# Actor_6_Channel.net
KiCad netlist of a schematic drawn in EAGLE
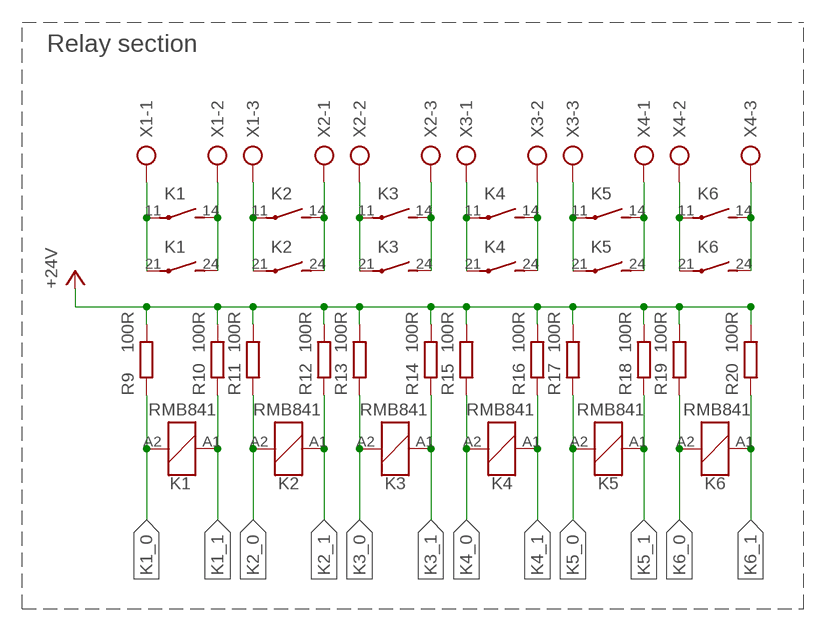
[diagram p0: schematic, sheet 1, part 1 of 2]
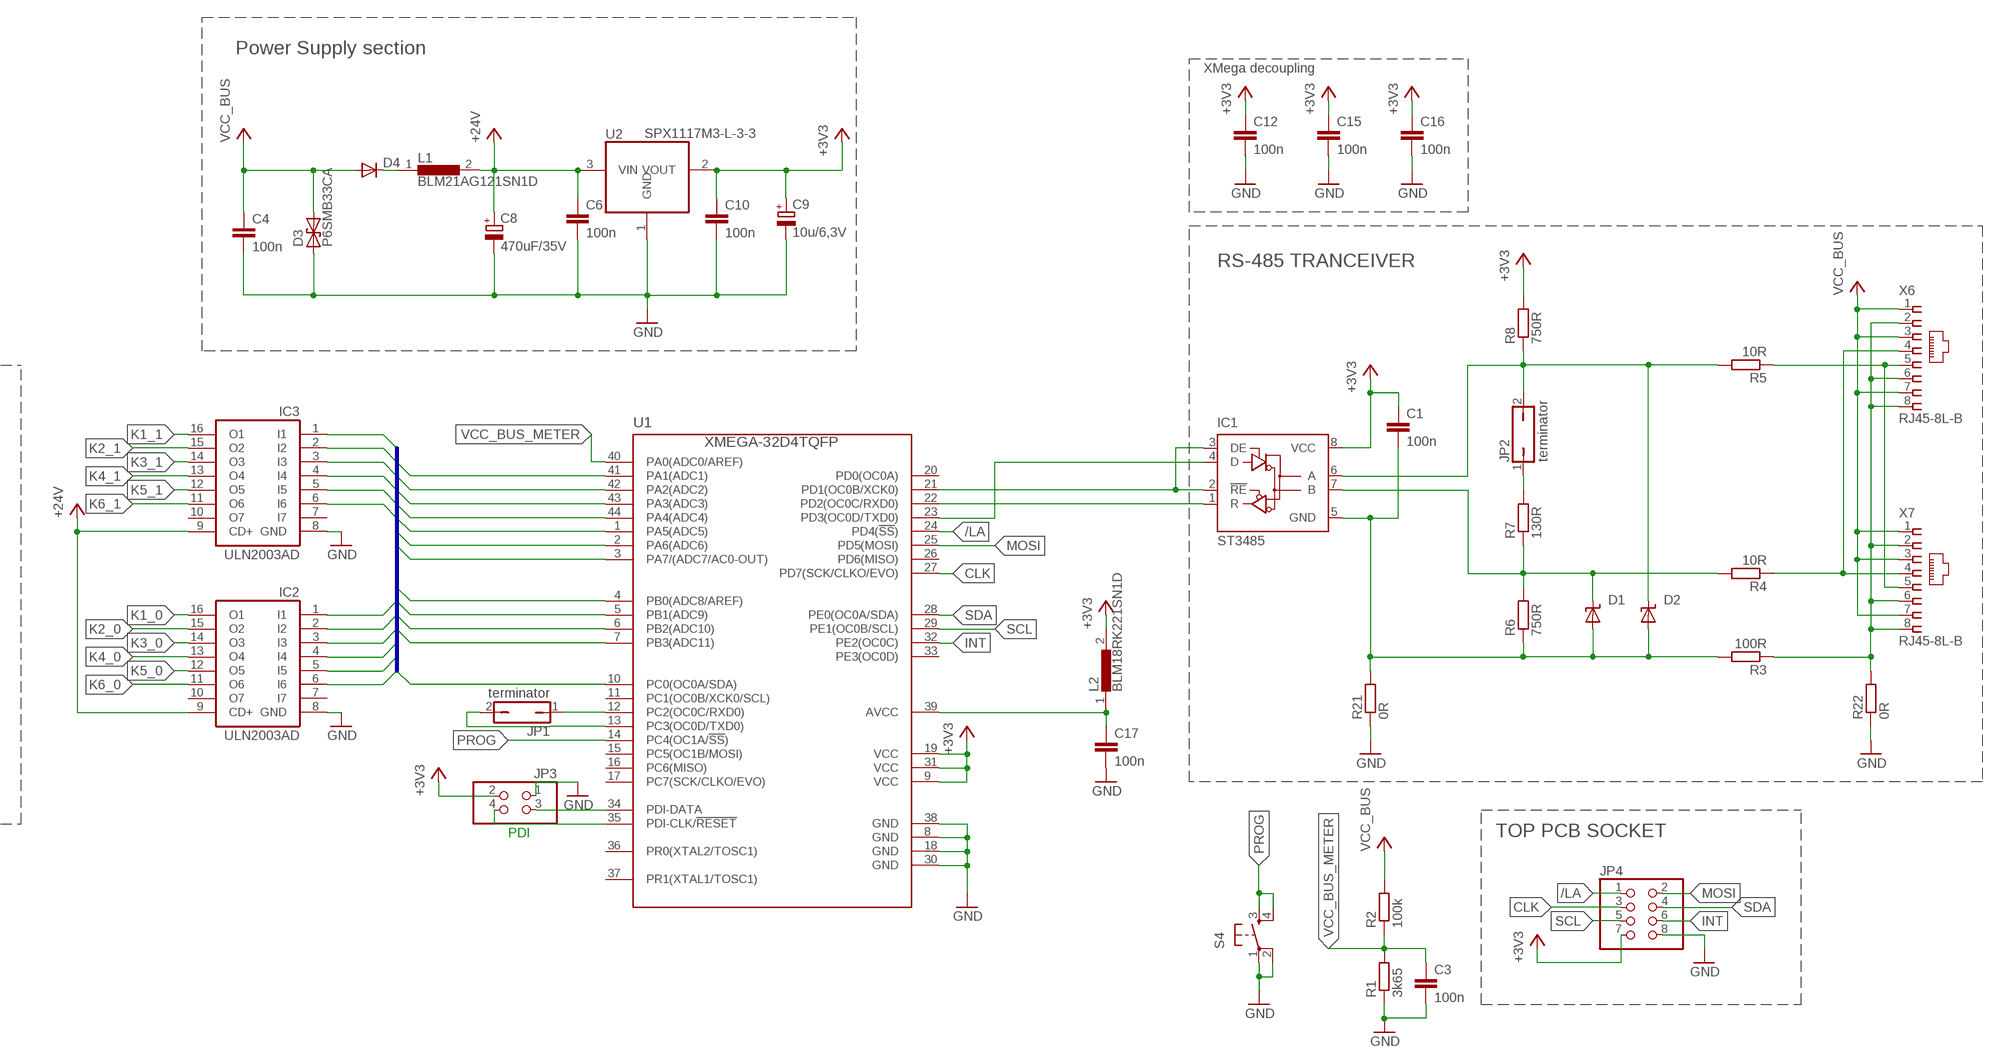
[diagram p1: schematic, sheet 1, part 2 of 2]

(export (version "E")
  (design (tool "Eeschema 10.0.6"))
  (components
    (comp (ref "C1")
      (value "100n")
      (footprint "eagle-import:C0603K")
      (libsource (lib "eagle-import") (part "C-EUC0603K"))
    )
    (comp (ref "C3")
      (value "100n")
      (footprint "eagle-import:C0603K")
      (libsource (lib "eagle-import") (part "C-EUC0603K"))
    )
    (comp (ref "C4")
      (value "100n")
      (footprint "eagle-import:C0603K")
      (libsource (lib "eagle-import") (part "C-EUC0603K"))
    )
    (comp (ref "C6")
      (value "100n")
      (footprint "eagle-import:C0603K")
      (libsource (lib "eagle-import") (part "C-EUC0603K"))
    )
    (comp (ref "C8")
      (value "470uF/35V")
      (footprint "eagle-import:E5-10,5")
      (libsource (lib "eagle-import") (part "CPOL-EUE5-10.5"))
    )
    (comp (ref "C9")
      (value "10u/6,3V")
      (footprint "eagle-import:E2-4")
      (libsource (lib "eagle-import") (part "CPOL-EUE2-4"))
    )
    (comp (ref "C10")
      (value "100n")
      (footprint "eagle-import:C0603K")
      (libsource (lib "eagle-import") (part "C-EUC0603K"))
    )
    (comp (ref "C12")
      (value "100n")
      (footprint "eagle-import:C0603K")
      (libsource (lib "eagle-import") (part "C-EUC0603K"))
    )
    (comp (ref "C15")
      (value "100n")
      (footprint "eagle-import:C0603K")
      (libsource (lib "eagle-import") (part "C-EUC0603K"))
    )
    (comp (ref "C16")
      (value "100n")
      (footprint "eagle-import:C0603K")
      (libsource (lib "eagle-import") (part "C-EUC0603K"))
    )
    (comp (ref "C17")
      (value "100n")
      (footprint "eagle-import:C0603K")
      (libsource (lib "eagle-import") (part "C-EUC0603K"))
    )
    (comp (ref "D1")
      (value "SUPPRESSOR-SMBJ")
      (footprint "eagle-import:SMBJ")
      (libsource (lib "eagle-import") (part "SUPPRESSOR-SMBJ"))
    )
    (comp (ref "D2")
      (value "SUPPRESSOR-SMBJ")
      (footprint "eagle-import:SMBJ")
      (libsource (lib "eagle-import") (part "SUPPRESSOR-SMBJ"))
    )
    (comp (ref "D3")
      (value "P6SMB33CA")
      (footprint "eagle-import:DO214AA")
      (libsource (lib "eagle-import") (part "P6KEXXCSMD"))
    )
    (comp (ref "D4")
      (value "DIODE-DO214AA")
      (footprint "eagle-import:DO214AA")
      (libsource (lib "eagle-import") (part "DIODE-DO214AA"))
    )
    (comp (ref "IC1")
      (value "ST3485")
      (footprint "eagle-import:D_R-PDSO-G8")
      (libsource (lib "eagle-import") (part "75176AD"))
    )
    (comp (ref "IC2")
      (value "ULN2003AD")
      (footprint "eagle-import:SO16")
      (libsource (lib "eagle-import") (part "ULN2003AD"))
    )
    (comp (ref "IC3")
      (value "ULN2003AD")
      (footprint "eagle-import:SO16")
      (libsource (lib "eagle-import") (part "ULN2003AD"))
    )
    (comp (ref "JP1")
      (value "terminator")
      (footprint "eagle-import:JP1")
      (libsource (lib "eagle-import") (part "JP1Q"))
    )
    (comp (ref "JP2")
      (value "terminator")
      (footprint "eagle-import:JP1")
      (libsource (lib "eagle-import") (part "JP1Q"))
    )
    (comp (ref "JP3")
      (value "PINHD-2X2")
      (footprint "eagle-import:2X02")
      (libsource (lib "eagle-import") (part "PINHD-2X2"))
    )
    (comp (ref "JP4")
      (value "PINHD-2X4")
      (footprint "eagle-import:2X04")
      (libsource (lib "eagle-import") (part "PINHD-2X4"))
    )
    (comp (ref "K1")
      (value "RMB841")
      (footprint "eagle-import:RT2N_O")
      (libsource (lib "eagle-import") (part "RT44?4730"))
    )
    (comp (ref "K2")
      (value "RMB841")
      (footprint "eagle-import:RT2N_O")
      (fields (field (name "OC_FARNELL") "unknown") (field (name "OC_NEWARK") "unknown"))
      (libsource (lib "eagle-import") (part "RT44?4730"))
    )
    (comp (ref "K3")
      (value "RMB841")
      (footprint "eagle-import:RT2N_O")
      (fields (field (name "OC_FARNELL") "unknown") (field (name "OC_NEWARK") "unknown"))
      (libsource (lib "eagle-import") (part "RT44?4730"))
    )
    (comp (ref "K4")
      (value "RMB841")
      (footprint "eagle-import:RT2N_O")
      (fields (field (name "OC_FARNELL") "unknown") (field (name "OC_NEWARK") "unknown"))
      (libsource (lib "eagle-import") (part "RT44?4730"))
    )
    (comp (ref "K5")
      (value "RMB841")
      (footprint "eagle-import:RT2N_O")
      (fields (field (name "OC_FARNELL") "unknown") (field (name "OC_NEWARK") "unknown"))
      (libsource (lib "eagle-import") (part "RT44?4730"))
    )
    (comp (ref "K6")
      (value "RMB841")
      (footprint "eagle-import:RT2N_O")
      (fields (field (name "OC_FARNELL") "unknown") (field (name "OC_NEWARK") "unknown"))
      (libsource (lib "eagle-import") (part "RT44?4730"))
    )
    (comp (ref "L1")
      (value "BLM21AG121SN1D")
      (footprint "eagle-import:805")
      (libsource (lib "eagle-import") (part "BLM21AG121SN1D"))
    )
    (comp (ref "L2")
      (value "BLM18RK221SN1D")
      (footprint "eagle-import:0603")
      (libsource (lib "eagle-import") (part "BLM18RK221SN1D"))
    )
    (comp (ref "R1")
      (value "3k65")
      (footprint "eagle-import:R0603")
      (libsource (lib "eagle-import") (part "R-EU_R0603"))
    )
    (comp (ref "R2")
      (value "100k")
      (footprint "eagle-import:R0603")
      (libsource (lib "eagle-import") (part "R-EU_R0603"))
    )
    (comp (ref "R3")
      (value "100R")
      (footprint "eagle-import:R0603")
      (libsource (lib "eagle-import") (part "R-EU_R0603"))
    )
    (comp (ref "R4")
      (value "10R")
      (footprint "eagle-import:R0603")
      (libsource (lib "eagle-import") (part "R-EU_R0603"))
    )
    (comp (ref "R5")
      (value "10R")
      (footprint "eagle-import:R0603")
      (libsource (lib "eagle-import") (part "R-EU_R0603"))
    )
    (comp (ref "R6")
      (value "750R")
      (footprint "eagle-import:M1206")
      (libsource (lib "eagle-import") (part "R-EU_M1206"))
    )
    (comp (ref "R7")
      (value "130R")
      (footprint "eagle-import:R0603")
      (libsource (lib "eagle-import") (part "R-EU_R0603"))
    )
    (comp (ref "R8")
      (value "750R")
      (footprint "eagle-import:R0603")
      (libsource (lib "eagle-import") (part "R-EU_R0603"))
    )
    (comp (ref "R9")
      (value "100R")
      (footprint "eagle-import:R0603")
      (libsource (lib "eagle-import") (part "R-EU_R0603"))
    )
    (comp (ref "R10")
      (value "100R")
      (footprint "eagle-import:R0603")
      (libsource (lib "eagle-import") (part "R-EU_R0603"))
    )
    (comp (ref "R11")
      (value "100R")
      (footprint "eagle-import:R0603")
      (libsource (lib "eagle-import") (part "R-EU_R0603"))
    )
    (comp (ref "R12")
      (value "100R")
      (footprint "eagle-import:R0603")
      (libsource (lib "eagle-import") (part "R-EU_R0603"))
    )
    (comp (ref "R13")
      (value "100R")
      (footprint "eagle-import:R0603")
      (libsource (lib "eagle-import") (part "R-EU_R0603"))
    )
    (comp (ref "R14")
      (value "100R")
      (footprint "eagle-import:R0603")
      (libsource (lib "eagle-import") (part "R-EU_R0603"))
    )
    (comp (ref "R15")
      (value "100R")
      (footprint "eagle-import:R0603")
      (libsource (lib "eagle-import") (part "R-EU_R0603"))
    )
    (comp (ref "R16")
      (value "100R")
      (footprint "eagle-import:R0603")
      (libsource (lib "eagle-import") (part "R-EU_R0603"))
    )
    (comp (ref "R17")
      (value "100R")
      (footprint "eagle-import:R0603")
      (libsource (lib "eagle-import") (part "R-EU_R0603"))
    )
    (comp (ref "R18")
      (value "100R")
      (footprint "eagle-import:R0603")
      (libsource (lib "eagle-import") (part "R-EU_R0603"))
    )
    (comp (ref "R19")
      (value "100R")
      (footprint "eagle-import:R0603")
      (libsource (lib "eagle-import") (part "R-EU_R0603"))
    )
    (comp (ref "R20")
      (value "100R")
      (footprint "eagle-import:R0603")
      (libsource (lib "eagle-import") (part "R-EU_R0603"))
    )
    (comp (ref "R21")
      (value "0R")
      (footprint "eagle-import:R0603")
      (libsource (lib "eagle-import") (part "R-EU_R0603"))
    )
    (comp (ref "R22")
      (value "0R")
      (footprint "eagle-import:R0603")
      (libsource (lib "eagle-import") (part "R-EU_R0603"))
    )
    (comp (ref "S4")
      (value "SPARKFUN_TAC_SWITCHPTH")
      (footprint "eagle-import:SPARKFUN_TACTILE-PTH")
      (libsource (lib "eagle-import") (part "SPARKFUN_TAC_SWITCHPTH"))
    )
    (comp (ref "U1")
      (value "XMEGA-32D4TQFP")
      (footprint "eagle-import:TQFP44")
      (libsource (lib "eagle-import") (part "XMEGA-D4TQFP"))
    )
    (comp (ref "U2")
      (value "SPX1117M3-L-3-3")
      (footprint "eagle-import:SOT223")
      (fields (field (name "MPN") "REG1117"))
      (libsource (lib "eagle-import") (part "REG1117"))
    )
    (comp (ref "X1")
      (value "MKDS_5/3-7,5")
      (footprint "eagle-import:MKDS_5_-750")
      (libsource (lib "eagle-import") (part "MKDS_5/3-7,5"))
    )
    (comp (ref "X2")
      (value "MKDS_5/3-7,5")
      (footprint "eagle-import:MKDS_5_-750")
      (libsource (lib "eagle-import") (part "MKDS_5/3-7,5"))
    )
    (comp (ref "X3")
      (value "MKDS_5/3-7,5")
      (footprint "eagle-import:MKDS_5_-750")
      (libsource (lib "eagle-import") (part "MKDS_5/3-7,5"))
    )
    (comp (ref "X4")
      (value "MKDS_5/3-7,5")
      (footprint "eagle-import:MKDS_5_-750")
      (libsource (lib "eagle-import") (part "MKDS_5/3-7,5"))
    )
    (comp (ref "X6")
      (value "RJ45-8L-B")
      (footprint "eagle-import:RJ45-NO-SHIELD")
      (fields (field (name "MF") "TYCO ELECTRONICS"))
      (libsource (lib "eagle-import") (part "RJ45-8L-B"))
    )
    (comp (ref "X7")
      (value "RJ45-8L-B")
      (footprint "eagle-import:RJ45-NO-SHIELD")
      (fields (field (name "MF") "TYCO ELECTRONICS"))
      (libsource (lib "eagle-import") (part "RJ45-8L-B"))
    )
  )
  (nets
    (net (code "1") (name "+3V3") (class "Default")
      (node (ref "C1") (pin "1") (pinfunction "1_1") (pintype "passive"))
      (node (ref "C10") (pin "1") (pinfunction "1_1") (pintype "passive"))
      (node (ref "C12") (pin "1") (pinfunction "1_1") (pintype "passive"))
      (node (ref "C15") (pin "1") (pinfunction "1_1") (pintype "passive"))
      (node (ref "C16") (pin "1") (pinfunction "1_1") (pintype "passive"))
      (node (ref "C9") (pin "+") (pinfunction "+_+") (pintype "passive"))
      (node (ref "IC1") (pin "8") (pinfunction "VCC_8") (pintype "power_in"))
      (node (ref "JP3") (pin "2") (pinfunction "2_2") (pintype "passive"))
      (node (ref "JP4") (pin "7") (pinfunction "7_7") (pintype "passive"))
      (node (ref "L2") (pin "2") (pinfunction "2_2") (pintype "passive"))
      (node (ref "R8") (pin "2") (pinfunction "2_2") (pintype "passive"))
      (node (ref "U1") (pin "19") (pinfunction "VCC_19") (pintype "power_in"))
      (node (ref "U1") (pin "31") (pinfunction "VCC_31") (pintype "power_in"))
      (node (ref "U1") (pin "9") (pinfunction "VCC_9") (pintype "power_in"))
      (node (ref "U2") (pin "2") (pinfunction "VOUT_2") (pintype "output"))
    )
    (net (code "2") (name "+24V") (class "Default")
      (node (ref "C6") (pin "1") (pinfunction "1_1") (pintype "passive"))
      (node (ref "C8") (pin "+") (pinfunction "+_+") (pintype "passive"))
      (node (ref "IC2") (pin "9") (pinfunction "CD+_9") (pintype "passive"))
      (node (ref "IC3") (pin "9") (pinfunction "CD+_9") (pintype "passive"))
      (node (ref "L1") (pin "2") (pinfunction "2_2") (pintype "passive"))
      (node (ref "R10") (pin "2") (pinfunction "2_2") (pintype "passive"))
      (node (ref "R11") (pin "2") (pinfunction "2_2") (pintype "passive"))
      (node (ref "R12") (pin "2") (pinfunction "2_2") (pintype "passive"))
      (node (ref "R13") (pin "2") (pinfunction "2_2") (pintype "passive"))
      (node (ref "R14") (pin "2") (pinfunction "2_2") (pintype "passive"))
      (node (ref "R15") (pin "2") (pinfunction "2_2") (pintype "passive"))
      (node (ref "R16") (pin "2") (pinfunction "2_2") (pintype "passive"))
      (node (ref "R17") (pin "2") (pinfunction "2_2") (pintype "passive"))
      (node (ref "R18") (pin "2") (pinfunction "2_2") (pintype "passive"))
      (node (ref "R19") (pin "2") (pinfunction "2_2") (pintype "passive"))
      (node (ref "R20") (pin "2") (pinfunction "2_2") (pintype "passive"))
      (node (ref "R9") (pin "2") (pinfunction "2_2") (pintype "passive"))
      (node (ref "U2") (pin "3") (pinfunction "VIN_3") (pintype "input"))
    )
    (net (code "3") (name "/PA1") (class "Default")
      (node (ref "IC3") (pin "6") (pinfunction "I6_6") (pintype "input"))
      (node (ref "U1") (pin "41") (pinfunction "PA1(ADC1)_41") (pintype "bidirectional"))
    )
    (net (code "4") (name "/PA2") (class "Default")
      (node (ref "IC3") (pin "5") (pinfunction "I5_5") (pintype "input"))
      (node (ref "U1") (pin "42") (pinfunction "PA2(ADC2)_42") (pintype "bidirectional"))
    )
    (net (code "5") (name "/PA3") (class "Default")
      (node (ref "IC3") (pin "4") (pinfunction "I4_4") (pintype "input"))
      (node (ref "U1") (pin "43") (pinfunction "PA3(ADC3)_43") (pintype "bidirectional"))
    )
    (net (code "6") (name "/PA4") (class "Default")
      (node (ref "IC3") (pin "3") (pinfunction "I3_3") (pintype "input"))
      (node (ref "U1") (pin "44") (pinfunction "PA4(ADC4)_44") (pintype "bidirectional"))
    )
    (net (code "7") (name "/PA5") (class "Default")
      (node (ref "IC3") (pin "2") (pinfunction "I2_2") (pintype "input"))
      (node (ref "U1") (pin "1") (pinfunction "PA5(ADC5)_1") (pintype "bidirectional"))
    )
    (net (code "8") (name "/PA6") (class "Default")
      (node (ref "IC3") (pin "1") (pinfunction "I1_1") (pintype "input"))
      (node (ref "U1") (pin "2") (pinfunction "PA6(ADC6)_2") (pintype "bidirectional"))
    )
    (net (code "9") (name "/PA7") (class "Default")
      (node (ref "IC2") (pin "6") (pinfunction "I6_6") (pintype "input"))
      (node (ref "U1") (pin "3") (pinfunction "PA7/(ADC7/AC0-OUT)_3") (pintype "bidirectional"))
    )
    (net (code "10") (name "/PB0") (class "Default")
      (node (ref "IC2") (pin "5") (pinfunction "I5_5") (pintype "input"))
      (node (ref "U1") (pin "4") (pinfunction "PB0(ADC8/AREF)_4") (pintype "bidirectional"))
    )
    (net (code "11") (name "/PB1") (class "Default")
      (node (ref "IC2") (pin "4") (pinfunction "I4_4") (pintype "input"))
      (node (ref "U1") (pin "5") (pinfunction "PB1(ADC9)_5") (pintype "bidirectional"))
    )
    (net (code "12") (name "/PB2") (class "Default")
      (node (ref "IC2") (pin "3") (pinfunction "I3_3") (pintype "input"))
      (node (ref "U1") (pin "6") (pinfunction "PB2(ADC10)_6") (pintype "bidirectional"))
    )
    (net (code "13") (name "/PB3") (class "Default")
      (node (ref "IC2") (pin "2") (pinfunction "I2_2") (pintype "input"))
      (node (ref "U1") (pin "7") (pinfunction "PB3(ADC11)_7") (pintype "bidirectional"))
    )
    (net (code "14") (name "/PC0") (class "Default")
      (node (ref "IC2") (pin "1") (pinfunction "I1_1") (pintype "input"))
      (node (ref "U1") (pin "10") (pinfunction "PC0(OC0A/SDA)_10") (pintype "bidirectional"))
    )
    (net (code "15") (name "CLK") (class "Default")
      (node (ref "JP4") (pin "3") (pinfunction "3_3") (pintype "passive"))
      (node (ref "U1") (pin "27") (pinfunction "PD7(SCK/CLKO/EVO)_27") (pintype "bidirectional"))
    )
    (net (code "16") (name "GND") (class "Default")
      (node (ref "C10") (pin "2") (pinfunction "2_2") (pintype "passive"))
      (node (ref "C12") (pin "2") (pinfunction "2_2") (pintype "passive"))
      (node (ref "C15") (pin "2") (pinfunction "2_2") (pintype "passive"))
      (node (ref "C16") (pin "2") (pinfunction "2_2") (pintype "passive"))
      (node (ref "C17") (pin "2") (pinfunction "2_2") (pintype "passive"))
      (node (ref "C3") (pin "2") (pinfunction "2_2") (pintype "passive"))
      (node (ref "C4") (pin "2") (pinfunction "2_2") (pintype "passive"))
      (node (ref "C6") (pin "2") (pinfunction "2_2") (pintype "passive"))
      (node (ref "C8") (pin "-") (pinfunction "-_-") (pintype "passive"))
      (node (ref "C9") (pin "-") (pinfunction "-_-") (pintype "passive"))
      (node (ref "D3") (pin "A") (pinfunction "1_A") (pintype "passive"))
      (node (ref "IC2") (pin "8") (pinfunction "GND_8") (pintype "power_in"))
      (node (ref "IC3") (pin "8") (pinfunction "GND_8") (pintype "power_in"))
      (node (ref "JP3") (pin "1") (pinfunction "1_1") (pintype "passive"))
      (node (ref "JP4") (pin "8") (pinfunction "8_8") (pintype "passive"))
      (node (ref "R1") (pin "1") (pinfunction "1_1") (pintype "passive"))
      (node (ref "R21") (pin "1") (pinfunction "1_1") (pintype "passive"))
      (node (ref "R22") (pin "1") (pinfunction "1_1") (pintype "passive"))
      (node (ref "S4") (pin "1") (pinfunction "1_1") (pintype "passive"))
      (node (ref "S4") (pin "2") (pinfunction "2_2") (pintype "passive"))
      (node (ref "U1") (pin "18") (pinfunction "GND_18") (pintype "power_in"))
      (node (ref "U1") (pin "30") (pinfunction "GND_30") (pintype "power_in"))
      (node (ref "U1") (pin "38") (pinfunction "GND_38") (pintype "power_in"))
      (node (ref "U1") (pin "8") (pinfunction "GND_8") (pintype "power_in"))
      (node (ref "U2") (pin "1") (pinfunction "GND_1") (pintype "power_in"))
    )
    (net (code "17") (name "INT") (class "Default")
      (node (ref "JP4") (pin "6") (pinfunction "6_6") (pintype "passive"))
      (node (ref "U1") (pin "32") (pinfunction "PE2(OC0C)_32") (pintype "bidirectional"))
    )
    (net (code "18") (name "K1_0") (class "Default")
      (node (ref "IC2") (pin "16") (pinfunction "O1_16") (pintype "open_collector"))
      (node (ref "K1") (pin "A2") (pinfunction "1_A2") (pintype "passive"))
      (node (ref "R9") (pin "1") (pinfunction "1_1") (pintype "passive"))
    )
    (net (code "19") (name "K1_1") (class "Default")
      (node (ref "IC3") (pin "16") (pinfunction "O1_16") (pintype "open_collector"))
      (node (ref "K1") (pin "A1") (pinfunction "2_A1") (pintype "passive"))
      (node (ref "R10") (pin "1") (pinfunction "1_1") (pintype "passive"))
    )
    (net (code "20") (name "K2_0") (class "Default")
      (node (ref "IC2") (pin "15") (pinfunction "O2_15") (pintype "open_collector"))
      (node (ref "K2") (pin "A2") (pinfunction "1_A2") (pintype "passive"))
      (node (ref "R11") (pin "1") (pinfunction "1_1") (pintype "passive"))
    )
    (net (code "21") (name "K2_1") (class "Default")
      (node (ref "IC3") (pin "15") (pinfunction "O2_15") (pintype "open_collector"))
      (node (ref "K2") (pin "A1") (pinfunction "2_A1") (pintype "passive"))
      (node (ref "R12") (pin "1") (pinfunction "1_1") (pintype "passive"))
    )
    (net (code "22") (name "K3_0") (class "Default")
      (node (ref "IC2") (pin "14") (pinfunction "O3_14") (pintype "open_collector"))
      (node (ref "K3") (pin "A2") (pinfunction "1_A2") (pintype "passive"))
      (node (ref "R13") (pin "1") (pinfunction "1_1") (pintype "passive"))
    )
    (net (code "23") (name "K3_1") (class "Default")
      (node (ref "IC3") (pin "14") (pinfunction "O3_14") (pintype "open_collector"))
      (node (ref "K3") (pin "A1") (pinfunction "2_A1") (pintype "passive"))
      (node (ref "R14") (pin "1") (pinfunction "1_1") (pintype "passive"))
    )
    (net (code "24") (name "K4_0") (class "Default")
      (node (ref "IC2") (pin "13") (pinfunction "O4_13") (pintype "open_collector"))
      (node (ref "K4") (pin "A2") (pinfunction "1_A2") (pintype "passive"))
      (node (ref "R15") (pin "1") (pinfunction "1_1") (pintype "passive"))
    )
    (net (code "25") (name "K4_1") (class "Default")
      (node (ref "IC3") (pin "13") (pinfunction "O4_13") (pintype "open_collector"))
      (node (ref "K4") (pin "A1") (pinfunction "2_A1") (pintype "passive"))
      (node (ref "R16") (pin "1") (pinfunction "1_1") (pintype "passive"))
    )
    (net (code "26") (name "K5_0") (class "Default")
      (node (ref "IC2") (pin "12") (pinfunction "O5_12") (pintype "open_collector"))
      (node (ref "K5") (pin "A2") (pinfunction "1_A2") (pintype "passive"))
      (node (ref "R17") (pin "1") (pinfunction "1_1") (pintype "passive"))
    )
    (net (code "27") (name "K5_1") (class "Default")
      (node (ref "IC3") (pin "12") (pinfunction "O5_12") (pintype "open_collector"))
      (node (ref "K5") (pin "A1") (pinfunction "2_A1") (pintype "passive"))
      (node (ref "R18") (pin "1") (pinfunction "1_1") (pintype "passive"))
    )
    (net (code "28") (name "K6_0") (class "Default")
      (node (ref "IC2") (pin "11") (pinfunction "O6_11") (pintype "open_collector"))
      (node (ref "K6") (pin "A2") (pinfunction "1_A2") (pintype "passive"))
      (node (ref "R19") (pin "1") (pinfunction "1_1") (pintype "passive"))
    )
    (net (code "29") (name "K6_1") (class "Default")
      (node (ref "IC3") (pin "11") (pinfunction "O6_11") (pintype "open_collector"))
      (node (ref "K6") (pin "A1") (pinfunction "2_A1") (pintype "passive"))
      (node (ref "R20") (pin "1") (pinfunction "1_1") (pintype "passive"))
    )
    (net (code "30") (name "MOSI") (class "Default")
      (node (ref "JP4") (pin "2") (pinfunction "2_2") (pintype "passive"))
      (node (ref "U1") (pin "25") (pinfunction "PD5(MOSI)_25") (pintype "bidirectional"))
    )
    (net (code "31") (name "Net-(D4-PadC)") (class "Default")
      (node (ref "D4") (pin "C") (pinfunction "C_C") (pintype "passive"))
      (node (ref "L1") (pin "1") (pinfunction "1_1") (pintype "passive"))
    )
    (net (code "32") (name "Net-(IC1-A)") (class "Default")
      (node (ref "D2") (pin "C") (pinfunction "C_C") (pintype "passive"))
      (node (ref "IC1") (pin "6") (pinfunction "A_6") (pintype "output"))
      (node (ref "JP2") (pin "2") (pinfunction "2_2") (pintype "passive"))
      (node (ref "R5") (pin "2") (pinfunction "2_2") (pintype "passive"))
      (node (ref "R8") (pin "1") (pinfunction "1_1") (pintype "passive"))
    )
    (net (code "33") (name "Net-(IC1-B)") (class "Default")
      (node (ref "D1") (pin "C") (pinfunction "C_C") (pintype "passive"))
      (node (ref "IC1") (pin "7") (pinfunction "B_7") (pintype "output"))
      (node (ref "R4") (pin "2") (pinfunction "2_2") (pintype "passive"))
      (node (ref "R6") (pin "2") (pinfunction "2_2") (pintype "passive"))
      (node (ref "R7") (pin "1") (pinfunction "1_1") (pintype "passive"))
    )
    (net (code "34") (name "Net-(IC1-D)") (class "Default")
      (node (ref "IC1") (pin "4") (pinfunction "D_4") (pintype "input"))
      (node (ref "U1") (pin "23") (pinfunction "PD3(OC0D/TXD0)_23") (pintype "bidirectional"))
    )
    (net (code "35") (name "Net-(IC1-DE)") (class "Default")
      (node (ref "IC1") (pin "2") (pinfunction "~{RE}_2") (pintype "input"))
      (node (ref "IC1") (pin "3") (pinfunction "DE_3") (pintype "input"))
      (node (ref "U1") (pin "21") (pinfunction "PD1(OC0B/XCK0)_21") (pintype "bidirectional"))
    )
    (net (code "36") (name "Net-(IC1-GND)") (class "Default")
      (node (ref "C1") (pin "2") (pinfunction "2_2") (pintype "passive"))
      (node (ref "D1") (pin "A") (pinfunction "A_A") (pintype "passive"))
      (node (ref "D2") (pin "A") (pinfunction "A_A") (pintype "passive"))
      (node (ref "IC1") (pin "5") (pinfunction "GND_5") (pintype "power_in"))
      (node (ref "R21") (pin "2") (pinfunction "2_2") (pintype "passive"))
      (node (ref "R3") (pin "2") (pinfunction "2_2") (pintype "passive"))
      (node (ref "R6") (pin "1") (pinfunction "1_1") (pintype "passive"))
    )
    (net (code "37") (name "Net-(IC1-R)") (class "Default")
      (node (ref "IC1") (pin "1") (pinfunction "R_1") (pintype "input"))
      (node (ref "U1") (pin "22") (pinfunction "PD2(OC0C/RXD0)_22") (pintype "bidirectional"))
    )
    (net (code "38") (name "Net-(JP2-Pad1)") (class "Default")
      (node (ref "JP2") (pin "1") (pinfunction "1_1") (pintype "passive"))
      (node (ref "R7") (pin "2") (pinfunction "2_2") (pintype "passive"))
    )
    (net (code "39") (name "Net-(K1B-P)") (class "Default")
      (node (ref "K1") (pin "11") (pinfunction "P_11") (pintype "passive"))
      (node (ref "K1") (pin "21") (pinfunction "P_21") (pintype "passive"))
      (node (ref "X1") (pin "1") (pinfunction "KL_1") (pintype "passive"))
    )
    (net (code "40") (name "Net-(K1B-S)") (class "Default")
      (node (ref "K1") (pin "14") (pinfunction "S_14") (pintype "passive"))
      (node (ref "K1") (pin "24") (pinfunction "S_24") (pintype "passive"))
      (node (ref "X1") (pin "2") (pinfunction "KL_2") (pintype "passive"))
    )
    (net (code "41") (name "Net-(K2B-P)") (class "Default")
      (node (ref "K2") (pin "11") (pinfunction "P_11") (pintype "passive"))
      (node (ref "K2") (pin "21") (pinfunction "P_21") (pintype "passive"))
      (node (ref "X1") (pin "3") (pinfunction "KL_3") (pintype "passive"))
    )
    (net (code "42") (name "Net-(K2B-S)") (class "Default")
      (node (ref "K2") (pin "14") (pinfunction "S_14") (pintype "passive"))
      (node (ref "K2") (pin "24") (pinfunction "S_24") (pintype "passive"))
      (node (ref "X2") (pin "1") (pinfunction "KL_1") (pintype "passive"))
    )
    (net (code "43") (name "Net-(K3B-P)") (class "Default")
      (node (ref "K3") (pin "11") (pinfunction "P_11") (pintype "passive"))
      (node (ref "K3") (pin "21") (pinfunction "P_21") (pintype "passive"))
      (node (ref "X2") (pin "2") (pinfunction "KL_2") (pintype "passive"))
    )
    (net (code "44") (name "Net-(K3B-S)") (class "Default")
      (node (ref "K3") (pin "14") (pinfunction "S_14") (pintype "passive"))
      (node (ref "K3") (pin "24") (pinfunction "S_24") (pintype "passive"))
      (node (ref "X2") (pin "3") (pinfunction "KL_3") (pintype "passive"))
    )
    (net (code "45") (name "Net-(K4B-P)") (class "Default")
      (node (ref "K4") (pin "11") (pinfunction "P_11") (pintype "passive"))
      (node (ref "K4") (pin "21") (pinfunction "P_21") (pintype "passive"))
      (node (ref "X3") (pin "1") (pinfunction "KL_1") (pintype "passive"))
    )
    (net (code "46") (name "Net-(K4B-S)") (class "Default")
      (node (ref "K4") (pin "14") (pinfunction "S_14") (pintype "passive"))
      (node (ref "K4") (pin "24") (pinfunction "S_24") (pintype "passive"))
      (node (ref "X3") (pin "2") (pinfunction "KL_2") (pintype "passive"))
    )
    (net (code "47") (name "Net-(K5B-P)") (class "Default")
      (node (ref "K5") (pin "11") (pinfunction "P_11") (pintype "passive"))
      (node (ref "K5") (pin "21") (pinfunction "P_21") (pintype "passive"))
      (node (ref "X3") (pin "3") (pinfunction "KL_3") (pintype "passive"))
    )
    (net (code "48") (name "Net-(K5B-S)") (class "Default")
      (node (ref "K5") (pin "14") (pinfunction "S_14") (pintype "passive"))
      (node (ref "K5") (pin "24") (pinfunction "S_24") (pintype "passive"))
      (node (ref "X4") (pin "1") (pinfunction "KL_1") (pintype "passive"))
    )
    (net (code "49") (name "Net-(K6B-P)") (class "Default")
      (node (ref "K6") (pin "11") (pinfunction "P_11") (pintype "passive"))
      (node (ref "K6") (pin "21") (pinfunction "P_21") (pintype "passive"))
      (node (ref "X4") (pin "2") (pinfunction "KL_2") (pintype "passive"))
    )
    (net (code "50") (name "Net-(K6B-S)") (class "Default")
      (node (ref "K6") (pin "14") (pinfunction "S_14") (pintype "passive"))
      (node (ref "K6") (pin "24") (pinfunction "S_24") (pintype "passive"))
      (node (ref "X4") (pin "3") (pinfunction "KL_3") (pintype "passive"))
    )
    (net (code "51") (name "Net-(R4-Pad1)") (class "Default")
      (node (ref "R4") (pin "1") (pinfunction "1_1") (pintype "passive"))
      (node (ref "X6") (pin "4") (pinfunction "4_4") (pintype "passive"))
      (node (ref "X7") (pin "4") (pinfunction "4_4") (pintype "passive"))
    )
    (net (code "52") (name "Net-(R5-Pad1)") (class "Default")
      (node (ref "R5") (pin "1") (pinfunction "1_1") (pintype "passive"))
      (node (ref "X6") (pin "5") (pinfunction "5_5") (pintype "passive"))
      (node (ref "X7") (pin "5") (pinfunction "5_5") (pintype "passive"))
    )
    (net (code "53") (name "Net-(R22-Pad2)") (class "Default")
      (node (ref "R22") (pin "2") (pinfunction "2_2") (pintype "passive"))
      (node (ref "R3") (pin "1") (pinfunction "1_1") (pintype "passive"))
      (node (ref "X6") (pin "2") (pinfunction "2_2") (pintype "passive"))
      (node (ref "X6") (pin "6") (pinfunction "6_6") (pintype "passive"))
      (node (ref "X6") (pin "8") (pinfunction "8_8") (pintype "passive"))
      (node (ref "X7") (pin "2") (pinfunction "2_2") (pintype "passive"))
      (node (ref "X7") (pin "6") (pinfunction "6_6") (pintype "passive"))
      (node (ref "X7") (pin "8") (pinfunction "8_8") (pintype "passive"))
    )
    (net (code "54") (name "Net-(U1-AVCC)") (class "Default")
      (node (ref "C17") (pin "1") (pinfunction "1_1") (pintype "passive"))
      (node (ref "L2") (pin "1") (pinfunction "1_1") (pintype "passive"))
      (node (ref "U1") (pin "39") (pinfunction "AVCC_39") (pintype "power_in"))
    )
    (net (code "55") (name "Net-(U1-PC2(OC0C{slash}RXD0))") (class "Default")
      (node (ref "JP1") (pin "1") (pinfunction "1_1") (pintype "passive"))
      (node (ref "U1") (pin "12") (pinfunction "PC2(OC0C/RXD0)_12") (pintype "bidirectional"))
    )
    (net (code "56") (name "Net-(U1-PC3(OC0D{slash}TXD0))") (class "Default")
      (node (ref "JP1") (pin "2") (pinfunction "2_2") (pintype "passive"))
      (node (ref "U1") (pin "13") (pinfunction "PC3(OC0D/TXD0)_13") (pintype "bidirectional"))
    )
    (net (code "57") (name "Net-(U1-PDI-CLK{slash}~{RESET})") (class "Default")
      (node (ref "JP3") (pin "4") (pinfunction "4_4") (pintype "passive"))
      (node (ref "U1") (pin "35") (pinfunction "PDI-CLK/~{RESET}_35") (pintype "input"))
    )
    (net (code "58") (name "Net-(U1-PDI-DATA)") (class "Default")
      (node (ref "JP3") (pin "3") (pinfunction "3_3") (pintype "passive"))
      (node (ref "U1") (pin "34") (pinfunction "PDI-DATA_34") (pintype "bidirectional"))
    )
    (net (code "59") (name "PROG") (class "Default")
      (node (ref "S4") (pin "3") (pinfunction "3_3") (pintype "passive"))
      (node (ref "S4") (pin "4") (pinfunction "4_4") (pintype "passive"))
      (node (ref "U1") (pin "14") (pinfunction "PC4(OC1A/~{SS})_14") (pintype "bidirectional"))
    )
    (net (code "60") (name "SCL") (class "Default")
      (node (ref "JP4") (pin "5") (pinfunction "5_5") (pintype "passive"))
      (node (ref "U1") (pin "29") (pinfunction "PE1(OC0B/SCL)_29") (pintype "bidirectional"))
    )
    (net (code "61") (name "SDA") (class "Default")
      (node (ref "JP4") (pin "4") (pinfunction "4_4") (pintype "passive"))
      (node (ref "U1") (pin "28") (pinfunction "PE0(OC0A/SDA)_28") (pintype "bidirectional"))
    )
    (net (code "62") (name "VCC_BUS") (class "Default")
      (node (ref "C4") (pin "1") (pinfunction "1_1") (pintype "passive"))
      (node (ref "D3") (pin "C") (pinfunction "2_C") (pintype "passive"))
      (node (ref "D4") (pin "A") (pinfunction "A_A") (pintype "passive"))
      (node (ref "R2") (pin "2") (pinfunction "2_2") (pintype "passive"))
      (node (ref "X6") (pin "1") (pinfunction "1_1") (pintype "passive"))
      (node (ref "X6") (pin "3") (pinfunction "3_3") (pintype "passive"))
      (node (ref "X6") (pin "7") (pinfunction "7_7") (pintype "passive"))
      (node (ref "X7") (pin "1") (pinfunction "1_1") (pintype "passive"))
      (node (ref "X7") (pin "3") (pinfunction "3_3") (pintype "passive"))
      (node (ref "X7") (pin "7") (pinfunction "7_7") (pintype "passive"))
    )
    (net (code "63") (name "VCC_BUS_METER") (class "Default")
      (node (ref "C3") (pin "1") (pinfunction "1_1") (pintype "passive"))
      (node (ref "R1") (pin "2") (pinfunction "2_2") (pintype "passive"))
      (node (ref "R2") (pin "1") (pinfunction "1_1") (pintype "passive"))
      (node (ref "U1") (pin "40") (pinfunction "PA0(ADC0/AREF)_40") (pintype "bidirectional"))
    )
    (net (code "64") (name "unconnected-(IC2-I7-Pad7)") (class "Default")
      (node (ref "IC2") (pin "7") (pinfunction "I7_7") (pintype "input"))
    )
    (net (code "65") (name "unconnected-(IC2-O7-Pad10)") (class "Default")
      (node (ref "IC2") (pin "10") (pinfunction "O7_10") (pintype "open_collector"))
    )
    (net (code "66") (name "unconnected-(IC3-I7-Pad7)") (class "Default")
      (node (ref "IC3") (pin "7") (pinfunction "I7_7") (pintype "input"))
    )
    (net (code "67") (name "unconnected-(IC3-O7-Pad10)") (class "Default")
      (node (ref "IC3") (pin "10") (pinfunction "O7_10") (pintype "open_collector"))
    )
    (net (code "68") (name "unconnected-(U1-PC1(OC0B{slash}XCK0{slash}SCL)-Pad11)") (class "Default")
      (node (ref "U1") (pin "11") (pinfunction "PC1(OC0B/XCK0/SCL)_11") (pintype "bidirectional"))
    )
    (net (code "69") (name "unconnected-(U1-PC5(OC1B{slash}MOSI)-Pad15)") (class "Default")
      (node (ref "U1") (pin "15") (pinfunction "PC5(OC1B/MOSI)_15") (pintype "bidirectional"))
    )
    (net (code "70") (name "unconnected-(U1-PC6(MISO)-Pad16)") (class "Default")
      (node (ref "U1") (pin "16") (pinfunction "PC6(MISO)_16") (pintype "bidirectional"))
    )
    (net (code "71") (name "unconnected-(U1-PC7(SCK{slash}CLKO{slash}EVO)-Pad17)") (class "Default")
      (node (ref "U1") (pin "17") (pinfunction "PC7(SCK/CLKO/EVO)_17") (pintype "bidirectional"))
    )
    (net (code "72") (name "unconnected-(U1-PD0(OC0A)-Pad20)") (class "Default")
      (node (ref "U1") (pin "20") (pinfunction "PD0(OC0A)_20") (pintype "bidirectional"))
    )
    (net (code "73") (name "unconnected-(U1-PD6(MISO)-Pad26)") (class "Default")
      (node (ref "U1") (pin "26") (pinfunction "PD6(MISO)_26") (pintype "bidirectional"))
    )
    (net (code "74") (name "unconnected-(U1-PE3(OC0D)-Pad33)") (class "Default")
      (node (ref "U1") (pin "33") (pinfunction "PE3(OC0D)_33") (pintype "bidirectional"))
    )
    (net (code "75") (name "unconnected-(U1-PR0(XTAL2{slash}TOSC1)-Pad36)") (class "Default")
      (node (ref "U1") (pin "36") (pinfunction "PR0(XTAL2/TOSC1)_36") (pintype "bidirectional"))
    )
    (net (code "76") (name "unconnected-(U1-PR1(XTAL1{slash}TOSC1)-Pad37)") (class "Default")
      (node (ref "U1") (pin "37") (pinfunction "PR1(XTAL1/TOSC1)_37") (pintype "bidirectional"))
    )
    (net (code "77") (name "{slash}LA") (class "Default")
      (node (ref "JP4") (pin "1") (pinfunction "1_1") (pintype "passive"))
      (node (ref "U1") (pin "24") (pinfunction "PD4(~{SS})_24") (pintype "bidirectional"))
    )
  )
)
